# pcbmlf.net
KiCad netlist of a schematic drawn in EAGLE
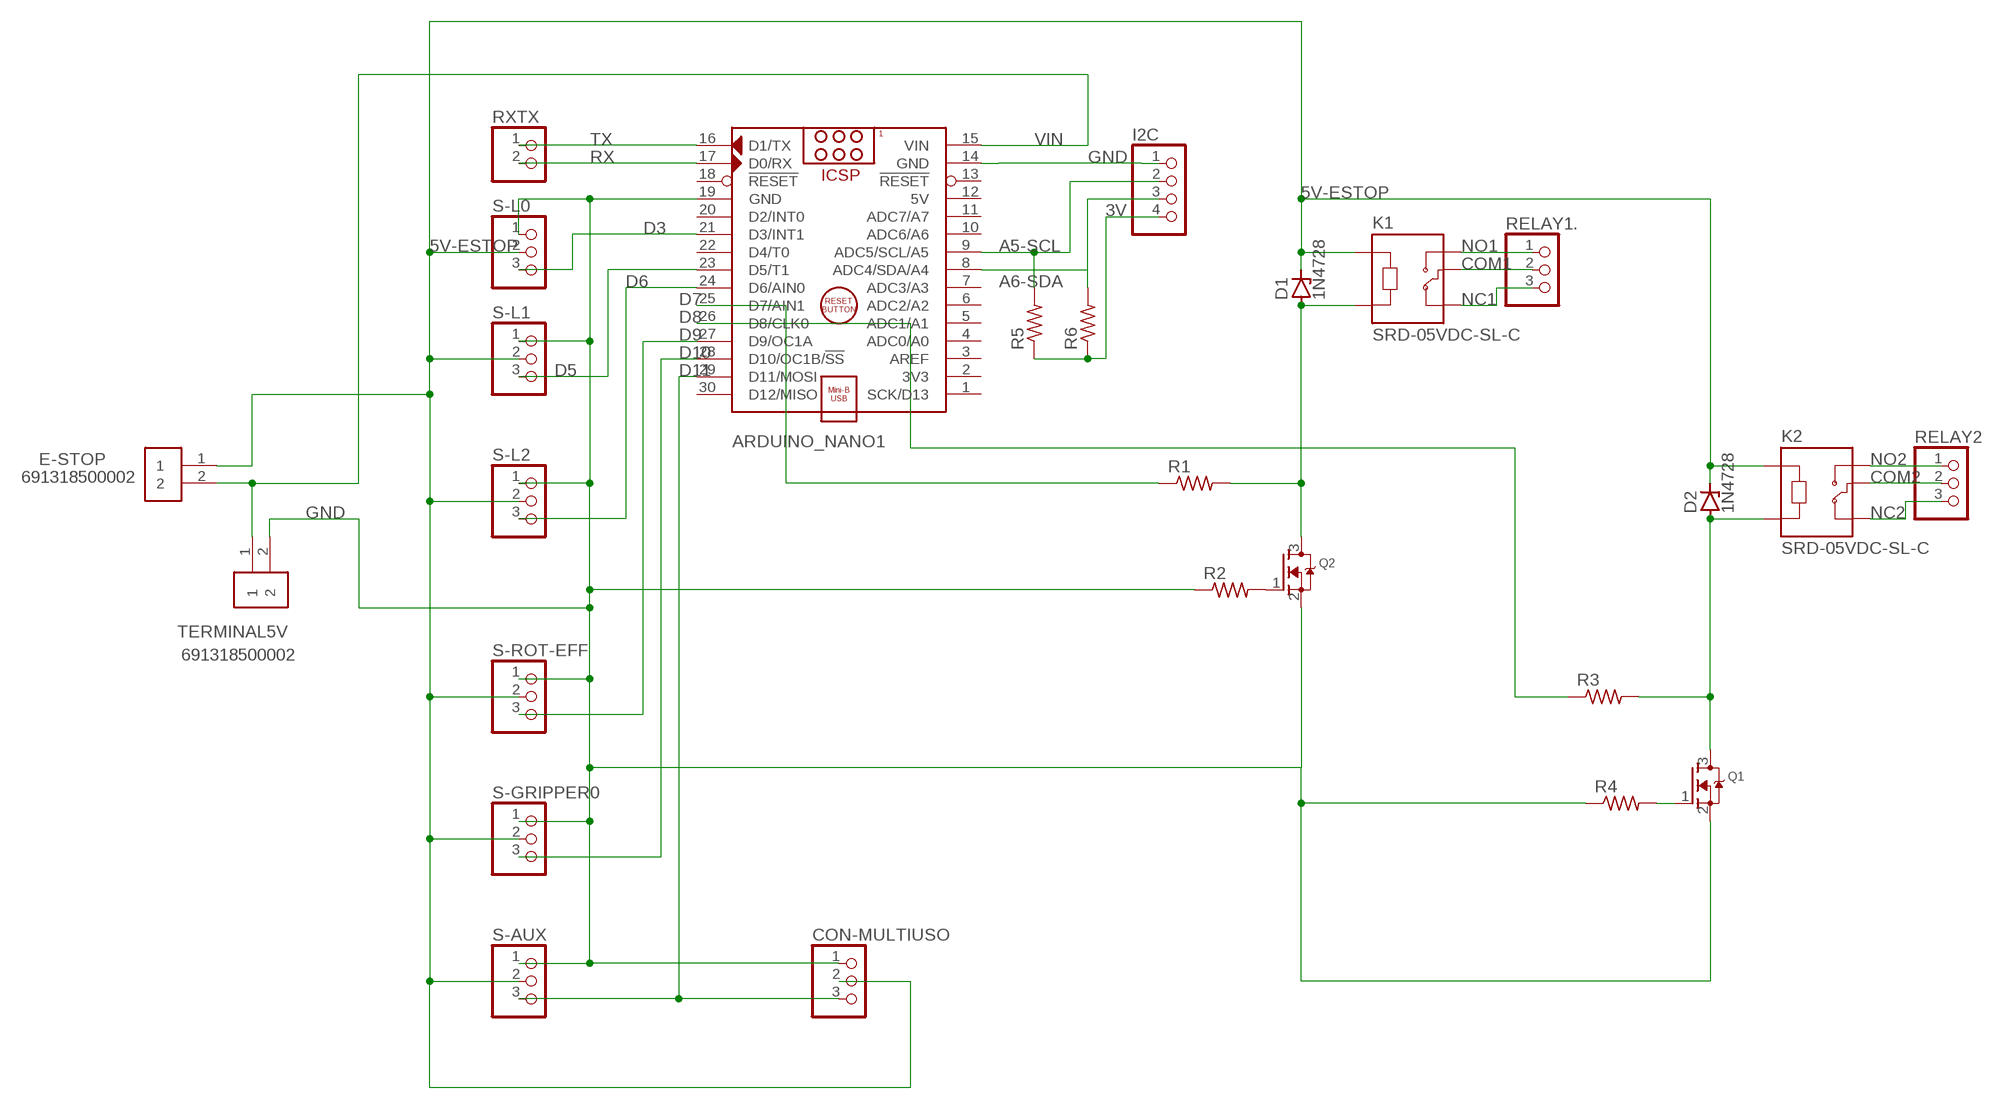
[diagram p0: schematic, sheet 1]

(export (version "E")
  (design (tool "Eeschema 10.0.6"))
  (components
    (comp (ref "ARDUINO_NANO1")
      (value "ARDUINO_NANO")
      (footprint "eagle-import:ARDUINO_NANO")
      (libsource (lib "eagle-import") (part "ARDUINO_NANO"))
    )
    (comp (ref "CON-MULTIUSO")
      (value "PINHD-1X3")
      (footprint "eagle-import:1X03")
      (libsource (lib "eagle-import") (part "PINHD-1X3"))
    )
    (comp (ref "D1")
      (value "1N4728")
      (footprint "eagle-import:DO41Z10")
      (libsource (lib "eagle-import") (part "1N4728"))
    )
    (comp (ref "D2")
      (value "1N4728")
      (footprint "eagle-import:DO41Z10")
      (libsource (lib "eagle-import") (part "1N4728"))
    )
    (comp (ref "E-STOP")
      (value "691318500002")
      (footprint "eagle-import:TERMINALBLOCK_PLUGGABLE-2-5.08MM")
      (fields
        (field (name "MANUFACTURER") "WURTH ELEKTRONIK")
        (field (name "MPN") " 691318500002  ")
        (field (name "CREATED_BY") "PCBLayout.com")
      )
      (libsource (lib "eagle-import") (part "691318500002"))
    )
    (comp (ref "I2C")
      (value "PINHD-1X4")
      (footprint "eagle-import:1X04")
      (libsource (lib "eagle-import") (part "PINHD-1X4"))
    )
    (comp (ref "K1")
      (value "SRD-05VDC-SL-C")
      (footprint "eagle-import:RELAY_SRD-05VDC-SL-C")
      (fields (field (name "MF") "Songle Relay"))
      (libsource (lib "eagle-import") (part "SRD-05VDC-SL-C"))
    )
    (comp (ref "K2")
      (value "SRD-05VDC-SL-C")
      (footprint "eagle-import:RELAY_SRD-05VDC-SL-C")
      (fields (field (name "MF") "Songle Relay") (field (name "SPICEPREFIX") "X"))
      (libsource (lib "eagle-import") (part "SRD-05VDC-SL-C"))
    )
    (comp (ref "Q1")
      (value "MOSFET-NWAVE")
      (footprint "eagle-import:SOT23-W")
      (libsource (lib "eagle-import") (part "MOSFET-NWAVE"))
    )
    (comp (ref "Q2")
      (value "MOSFET-NWAVE")
      (footprint "eagle-import:SOT23-W")
      (libsource (lib "eagle-import") (part "MOSFET-NWAVE"))
    )
    (comp (ref "R1")
      (value "R-US_R0805")
      (footprint "eagle-import:R0805")
      (libsource (lib "eagle-import") (part "R-US_R0805"))
    )
    (comp (ref "R2")
      (value "R-US_R0805")
      (footprint "eagle-import:R0805")
      (libsource (lib "eagle-import") (part "R-US_R0805"))
    )
    (comp (ref "R3")
      (value "R-US_R0805")
      (footprint "eagle-import:R0805")
      (libsource (lib "eagle-import") (part "R-US_R0805"))
    )
    (comp (ref "R4")
      (value "R-US_R0805")
      (footprint "eagle-import:R0805")
      (libsource (lib "eagle-import") (part "R-US_R0805"))
    )
    (comp (ref "R5")
      (value "R-US_R0805")
      (footprint "eagle-import:R0805")
      (libsource (lib "eagle-import") (part "R-US_R0805"))
    )
    (comp (ref "R6")
      (value "R-US_R0805")
      (footprint "eagle-import:R0805")
      (libsource (lib "eagle-import") (part "R-US_R0805"))
    )
    (comp (ref "RELAY1.")
      (value "PINHD-1X3")
      (footprint "eagle-import:1X03")
      (libsource (lib "eagle-import") (part "PINHD-1X3"))
    )
    (comp (ref "RELAY2")
      (value "PINHD-1X3")
      (footprint "eagle-import:1X03")
      (libsource (lib "eagle-import") (part "PINHD-1X3"))
    )
    (comp (ref "RXTX")
      (value "PINHD-1X2")
      (footprint "eagle-import:1X02")
      (libsource (lib "eagle-import") (part "PINHD-1X2"))
    )
    (comp (ref "S-AUX")
      (value "PINHD-1X3")
      (footprint "eagle-import:1X03")
      (libsource (lib "eagle-import") (part "PINHD-1X3"))
    )
    (comp (ref "S-GRIPPER0")
      (value "PINHD-1X3")
      (footprint "eagle-import:1X03")
      (libsource (lib "eagle-import") (part "PINHD-1X3"))
    )
    (comp (ref "S-L0")
      (value "PINHD-1X3")
      (footprint "eagle-import:1X03")
      (libsource (lib "eagle-import") (part "PINHD-1X3"))
    )
    (comp (ref "S-L1")
      (value "PINHD-1X3")
      (footprint "eagle-import:1X03")
      (libsource (lib "eagle-import") (part "PINHD-1X3"))
    )
    (comp (ref "S-L2")
      (value "PINHD-1X3")
      (footprint "eagle-import:1X03")
      (libsource (lib "eagle-import") (part "PINHD-1X3"))
    )
    (comp (ref "S-ROT-EFF")
      (value "PINHD-1X3")
      (footprint "eagle-import:1X03")
      (libsource (lib "eagle-import") (part "PINHD-1X3"))
    )
    (comp (ref "TERMINAL5V")
      (value "691318500002")
      (footprint "eagle-import:TERMINALBLOCK_PLUGGABLE-2-5.08MM")
      (fields
        (field (name "MANUFACTURER") "WURTH ELEKTRONIK")
        (field (name "MPN") " 691318500002  ")
        (field (name "CREATED_BY") "PCBLayout.com")
      )
      (libsource (lib "eagle-import") (part "691318500002"))
    )
  )
  (nets
    (net (code "1") (name "/3V") (class "Default")
      (node (ref "I2C") (pin "4") (pinfunction "4_4") (pintype "passive"))
      (node (ref "R5") (pin "1") (pinfunction "1_1") (pintype "passive"))
      (node (ref "R6") (pin "1") (pinfunction "1_1") (pintype "passive"))
    )
    (net (code "2") (name "/5V") (class "Default")
      (node (ref "ARDUINO_NANO1") (pin "12") (pinfunction "5V_12") (pintype "power_in"))
    )
    (net (code "3") (name "/5V-ESTOP") (class "Default")
      (node (ref "CON-MULTIUSO") (pin "2") (pinfunction "2_2") (pintype "passive"))
      (node (ref "D1") (pin "C") (pinfunction "C_C") (pintype "passive"))
      (node (ref "D2") (pin "C") (pinfunction "C_C") (pintype "passive"))
      (node (ref "E-STOP") (pin "1") (pinfunction "1_1") (pintype "passive"))
      (node (ref "K1") (pin "A1") (pinfunction "A1_A1") (pintype "passive"))
      (node (ref "K2") (pin "A1") (pinfunction "A1_A1") (pintype "passive"))
      (node (ref "S-AUX") (pin "2") (pinfunction "2_2") (pintype "passive"))
      (node (ref "S-GRIPPER0") (pin "2") (pinfunction "2_2") (pintype "passive"))
      (node (ref "S-L0") (pin "2") (pinfunction "2_2") (pintype "passive"))
      (node (ref "S-L1") (pin "2") (pinfunction "2_2") (pintype "passive"))
      (node (ref "S-L2") (pin "2") (pinfunction "2_2") (pintype "passive"))
      (node (ref "S-ROT-EFF") (pin "2") (pinfunction "2_2") (pintype "passive"))
    )
    (net (code "4") (name "/A5-SCL") (class "Default")
      (node (ref "ARDUINO_NANO1") (pin "9") (pinfunction "ADC5/SCL/A5_9") (pintype "bidirectional"))
      (node (ref "I2C") (pin "2") (pinfunction "2_2") (pintype "passive"))
      (node (ref "R5") (pin "2") (pinfunction "2_2") (pintype "passive"))
    )
    (net (code "5") (name "/A6-SDA") (class "Default")
      (node (ref "ARDUINO_NANO1") (pin "8") (pinfunction "ADC4/SDA/A4_8") (pintype "bidirectional"))
      (node (ref "I2C") (pin "3") (pinfunction "3_3") (pintype "passive"))
      (node (ref "R6") (pin "2") (pinfunction "2_2") (pintype "passive"))
    )
    (net (code "6") (name "/COM1") (class "Default")
      (node (ref "K1") (pin "COM") (pinfunction "COM_COM") (pintype "passive"))
      (node (ref "RELAY1.") (pin "2") (pinfunction "2_2") (pintype "passive"))
    )
    (net (code "7") (name "/COM2") (class "Default")
      (node (ref "K2") (pin "COM") (pinfunction "COM_COM") (pintype "passive"))
      (node (ref "RELAY2") (pin "2") (pinfunction "2_2") (pintype "passive"))
    )
    (net (code "8") (name "/D3") (class "Default")
      (node (ref "ARDUINO_NANO1") (pin "21") (pinfunction "D3/INT1_21") (pintype "bidirectional"))
      (node (ref "S-L0") (pin "3") (pinfunction "3_3") (pintype "passive"))
    )
    (net (code "9") (name "/D5") (class "Default")
      (node (ref "ARDUINO_NANO1") (pin "23") (pinfunction "D5/T1_23") (pintype "bidirectional"))
      (node (ref "S-L1") (pin "3") (pinfunction "3_3") (pintype "passive"))
    )
    (net (code "10") (name "/D6") (class "Default")
      (node (ref "ARDUINO_NANO1") (pin "24") (pinfunction "D6/AIN0_24") (pintype "bidirectional"))
      (node (ref "S-L2") (pin "3") (pinfunction "3_3") (pintype "passive"))
    )
    (net (code "11") (name "/D7") (class "Default")
      (node (ref "ARDUINO_NANO1") (pin "25") (pinfunction "D7/AIN1_25") (pintype "bidirectional"))
      (node (ref "R1") (pin "1") (pinfunction "1_1") (pintype "passive"))
    )
    (net (code "12") (name "/D8") (class "Default")
      (node (ref "ARDUINO_NANO1") (pin "26") (pinfunction "D8/CLK0_26") (pintype "bidirectional"))
      (node (ref "R3") (pin "1") (pinfunction "1_1") (pintype "passive"))
    )
    (net (code "13") (name "/D9") (class "Default")
      (node (ref "ARDUINO_NANO1") (pin "27") (pinfunction "D9/OC1A_27") (pintype "bidirectional"))
      (node (ref "S-ROT-EFF") (pin "3") (pinfunction "3_3") (pintype "passive"))
    )
    (net (code "14") (name "/D10") (class "Default")
      (node (ref "ARDUINO_NANO1") (pin "28") (pinfunction "D10/OC1B/~{SS}_28") (pintype "bidirectional"))
      (node (ref "S-GRIPPER0") (pin "3") (pinfunction "3_3") (pintype "passive"))
    )
    (net (code "15") (name "/D11") (class "Default")
      (node (ref "ARDUINO_NANO1") (pin "29") (pinfunction "D11/MOSI_29") (pintype "bidirectional"))
      (node (ref "CON-MULTIUSO") (pin "3") (pinfunction "3_3") (pintype "passive"))
      (node (ref "S-AUX") (pin "3") (pinfunction "3_3") (pintype "passive"))
    )
    (net (code "16") (name "/GND") (class "Default")
      (node (ref "ARDUINO_NANO1") (pin "14") (pinfunction "GND_14") (pintype "power_in"))
      (node (ref "ARDUINO_NANO1") (pin "19") (pinfunction "GND_19") (pintype "power_in"))
      (node (ref "CON-MULTIUSO") (pin "1") (pinfunction "1_1") (pintype "passive"))
      (node (ref "I2C") (pin "1") (pinfunction "1_1") (pintype "passive"))
      (node (ref "Q1") (pin "2") (pinfunction "S_2") (pintype "bidirectional"))
      (node (ref "Q2") (pin "2") (pinfunction "S_2") (pintype "bidirectional"))
      (node (ref "R2") (pin "1") (pinfunction "1_1") (pintype "passive"))
      (node (ref "R4") (pin "1") (pinfunction "1_1") (pintype "passive"))
      (node (ref "S-AUX") (pin "1") (pinfunction "1_1") (pintype "passive"))
      (node (ref "S-GRIPPER0") (pin "1") (pinfunction "1_1") (pintype "passive"))
      (node (ref "S-L0") (pin "1") (pinfunction "1_1") (pintype "passive"))
      (node (ref "S-L1") (pin "1") (pinfunction "1_1") (pintype "passive"))
      (node (ref "S-L2") (pin "1") (pinfunction "1_1") (pintype "passive"))
      (node (ref "S-ROT-EFF") (pin "1") (pinfunction "1_1") (pintype "passive"))
      (node (ref "TERMINAL5V") (pin "2") (pinfunction "2_2") (pintype "passive"))
    )
    (net (code "17") (name "/NC1") (class "Default")
      (node (ref "K1") (pin "NC") (pinfunction "NC_NC") (pintype "passive"))
      (node (ref "RELAY1.") (pin "3") (pinfunction "3_3") (pintype "passive"))
    )
    (net (code "18") (name "/NC2") (class "Default")
      (node (ref "K2") (pin "NC") (pinfunction "NC_NC") (pintype "passive"))
      (node (ref "RELAY2") (pin "3") (pinfunction "3_3") (pintype "passive"))
    )
    (net (code "19") (name "/NO1") (class "Default")
      (node (ref "K1") (pin "NO") (pinfunction "NO_NO") (pintype "passive"))
      (node (ref "RELAY1.") (pin "1") (pinfunction "1_1") (pintype "passive"))
    )
    (net (code "20") (name "/NO2") (class "Default")
      (node (ref "K2") (pin "NO") (pinfunction "NO_NO") (pintype "passive"))
      (node (ref "RELAY2") (pin "1") (pinfunction "1_1") (pintype "passive"))
    )
    (net (code "21") (name "/RX") (class "Default")
      (node (ref "ARDUINO_NANO1") (pin "17") (pinfunction "D0/RX_17") (pintype "bidirectional"))
      (node (ref "RXTX") (pin "2") (pinfunction "2_2") (pintype "passive"))
    )
    (net (code "22") (name "/TX") (class "Default")
      (node (ref "ARDUINO_NANO1") (pin "16") (pinfunction "D1/TX_16") (pintype "bidirectional"))
      (node (ref "RXTX") (pin "1") (pinfunction "1_1") (pintype "passive"))
    )
    (net (code "23") (name "/VIN") (class "Default")
      (node (ref "ARDUINO_NANO1") (pin "15") (pinfunction "VIN_15") (pintype "power_in"))
      (node (ref "E-STOP") (pin "2") (pinfunction "2_2") (pintype "passive"))
      (node (ref "TERMINAL5V") (pin "1") (pinfunction "1_1") (pintype "passive"))
    )
    (net (code "24") (name "Net-(Q1-D)") (class "Default")
      (node (ref "D2") (pin "A") (pinfunction "A_A") (pintype "passive"))
      (node (ref "K2") (pin "A2") (pinfunction "A2_A2") (pintype "passive"))
      (node (ref "Q1") (pin "3") (pinfunction "D_3") (pintype "bidirectional"))
      (node (ref "R3") (pin "2") (pinfunction "2_2") (pintype "passive"))
    )
    (net (code "25") (name "Net-(Q1-G)") (class "Default")
      (node (ref "Q1") (pin "1") (pinfunction "G_1") (pintype "bidirectional"))
      (node (ref "R4") (pin "2") (pinfunction "2_2") (pintype "passive"))
    )
    (net (code "26") (name "Net-(Q2-D)") (class "Default")
      (node (ref "D1") (pin "A") (pinfunction "A_A") (pintype "passive"))
      (node (ref "K1") (pin "A2") (pinfunction "A2_A2") (pintype "passive"))
      (node (ref "Q2") (pin "3") (pinfunction "D_3") (pintype "bidirectional"))
      (node (ref "R1") (pin "2") (pinfunction "2_2") (pintype "passive"))
    )
    (net (code "27") (name "Net-(Q2-G)") (class "Default")
      (node (ref "Q2") (pin "1") (pinfunction "G_1") (pintype "bidirectional"))
      (node (ref "R2") (pin "2") (pinfunction "2_2") (pintype "passive"))
    )
    (net (code "28") (name "unconnected-(ARDUINO_NANO1-3V3-Pad2)") (class "Default")
      (node (ref "ARDUINO_NANO1") (pin "2") (pinfunction "3V3_2") (pintype "output"))
    )
    (net (code "29") (name "unconnected-(ARDUINO_NANO1-ADC0{slash}A0-Pad4)") (class "Default")
      (node (ref "ARDUINO_NANO1") (pin "4") (pinfunction "ADC0/A0_4") (pintype "bidirectional"))
    )
    (net (code "30") (name "unconnected-(ARDUINO_NANO1-ADC1{slash}A1-Pad5)") (class "Default")
      (node (ref "ARDUINO_NANO1") (pin "5") (pinfunction "ADC1/A1_5") (pintype "bidirectional"))
    )
    (net (code "31") (name "unconnected-(ARDUINO_NANO1-ADC2{slash}A2-Pad6)") (class "Default")
      (node (ref "ARDUINO_NANO1") (pin "6") (pinfunction "ADC2/A2_6") (pintype "bidirectional"))
    )
    (net (code "32") (name "unconnected-(ARDUINO_NANO1-ADC3{slash}A3-Pad7)") (class "Default")
      (node (ref "ARDUINO_NANO1") (pin "7") (pinfunction "ADC3/A3_7") (pintype "bidirectional"))
    )
    (net (code "33") (name "unconnected-(ARDUINO_NANO1-ADC6{slash}A6-Pad10)") (class "Default")
      (node (ref "ARDUINO_NANO1") (pin "10") (pinfunction "ADC6/A6_10") (pintype "bidirectional"))
    )
    (net (code "34") (name "unconnected-(ARDUINO_NANO1-ADC7{slash}A7-Pad11)") (class "Default")
      (node (ref "ARDUINO_NANO1") (pin "11") (pinfunction "ADC7/A7_11") (pintype "bidirectional"))
    )
    (net (code "35") (name "unconnected-(ARDUINO_NANO1-AREF-Pad3)") (class "Default")
      (node (ref "ARDUINO_NANO1") (pin "3") (pinfunction "AREF_3") (pintype "input"))
    )
    (net (code "36") (name "unconnected-(ARDUINO_NANO1-D2{slash}INT0-Pad20)") (class "Default")
      (node (ref "ARDUINO_NANO1") (pin "20") (pinfunction "D2/INT0_20") (pintype "bidirectional"))
    )
    (net (code "37") (name "unconnected-(ARDUINO_NANO1-D4{slash}T0-Pad22)") (class "Default")
      (node (ref "ARDUINO_NANO1") (pin "22") (pinfunction "D4/T0_22") (pintype "bidirectional"))
    )
    (net (code "38") (name "unconnected-(ARDUINO_NANO1-D12{slash}MISO-Pad30)") (class "Default")
      (node (ref "ARDUINO_NANO1") (pin "30") (pinfunction "D12/MISO_30") (pintype "bidirectional"))
    )
    (net (code "39") (name "unconnected-(ARDUINO_NANO1-SCK{slash}D13-Pad1)") (class "Default")
      (node (ref "ARDUINO_NANO1") (pin "1") (pinfunction "SCK/D13_1") (pintype "bidirectional"))
    )
    (net (code "40") (name "unconnected-(ARDUINO_NANO1-~{RESET}-Pad13)") (class "Default")
      (node (ref "ARDUINO_NANO1") (pin "13") (pinfunction "~{RESET}_13") (pintype "input"))
    )
    (net (code "41") (name "unconnected-(ARDUINO_NANO1-~{RESET}-Pad18)") (class "Default")
      (node (ref "ARDUINO_NANO1") (pin "18") (pinfunction "~{RESET}_18") (pintype "input"))
    )
  )
)
